# KeyBoardPower.net
KiCad netlist of a schematic drawn in Altium Designer
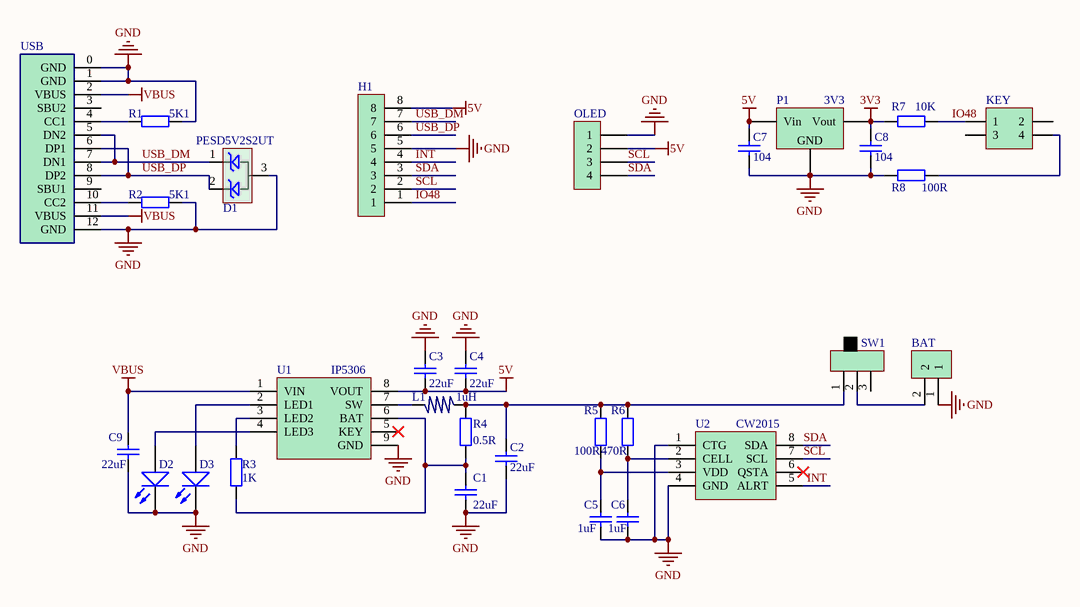
[diagram p0: KeyBoardPower.SchDoc]

(export (version "E")
  (design (tool "Eeschema 10.0.6"))
  (components
    (comp (ref "BAT")
      (value "PH2.0mm")
      (footprint "PH2.0_2P_SMT_L")
      (description "PH2.0")
      (libsource (lib "MT_Connector") (part "PH2.0mm_2P_SMT_L"))
    )
    (comp (ref "C1")
      (value "22uF")
      (footprint "0805")
      (description "贴片电容 0805")
      (libsource (lib "MT_Device") (part "CAP_0805"))
    )
    (comp (ref "C2")
      (value "22uF")
      (footprint "0805")
      (description "贴片电容 0805")
      (libsource (lib "MT_Device") (part "CAP_0805"))
    )
    (comp (ref "C3")
      (value "22uF")
      (footprint "0805")
      (description "贴片电容 0805")
      (libsource (lib "MT_Device") (part "CAP_0805"))
    )
    (comp (ref "C4")
      (value "22uF")
      (footprint "0805")
      (description "贴片电容 0805")
      (libsource (lib "MT_Device") (part "CAP_0805"))
    )
    (comp (ref "C5")
      (value "1uF")
      (footprint "0603")
      (description "贴片电容 0603")
      (libsource (lib "MT_Device") (part "CAP_0603"))
    )
    (comp (ref "C6")
      (value "1uF")
      (footprint "0603")
      (description "贴片电容 0603")
      (libsource (lib "MT_Device") (part "CAP_0603"))
    )
    (comp (ref "C7")
      (value "104")
      (footprint "0603")
      (description "贴片电容 0603")
      (libsource (lib "MT_Device") (part "CAP_0603"))
    )
    (comp (ref "C8")
      (value "104")
      (footprint "0603")
      (description "贴片电容 0603")
      (libsource (lib "MT_Device") (part "CAP_0603"))
    )
    (comp (ref "C9")
      (value "22uF")
      (footprint "0805")
      (description "贴片电容 0805")
      (libsource (lib "MT_Device") (part "CAP_0805"))
    )
    (comp (ref "D1")
      (value "PESD5V2S2UT")
      (footprint "SOT23")
      (description "ESD DIODE")
      (libsource (lib "MT_Device") (part "PESD5V2S2UT"))
    )
    (comp (ref "D2")
      (value "LED")
      (footprint "LED_0603")
      (description "LED 0603")
      (libsource (lib "MT_Device") (part "LED_0603"))
    )
    (comp (ref "D3")
      (value "LED")
      (footprint "LED_0603")
      (description "LED 0603")
      (libsource (lib "MT_Device") (part "LED_0603"))
    )
    (comp (ref "H1")
      (value "SH1.25mm_8P")
      (footprint "SH1.25MM_8P")
      (description "SH")
      (libsource (lib "MT_Connector") (part "SH1.25mm_8P"))
    )
    (comp (ref "KEY")
      (value "KEY")
      (footprint "KEY_DIP_6")
      (description "直插立式按键 6mm")
      (libsource (lib "MT_Device") (part "KEY_DIP_6"))
    )
    (comp (ref "L1")
      (value "1uH")
      (footprint "L_0420")
      (description "电感 0420")
      (libsource (lib "MT_Device") (part "L_0420"))
    )
    (comp (ref "OLED")
      (value "Header_2.54_4P")
      (footprint "HDR1_4P")
      (description "PinHeader 2.54")
      (libsource (lib "MT_Connector") (part "Header_2.54_4P"))
    )
    (comp (ref "P1")
      (value "3V3")
      (footprint "SOT23")
      (description "线性稳压器")
      (libsource (lib "MT_Device") (part "LDO_XC6206P332MR"))
    )
    (comp (ref "R1")
      (value "5K1")
      (footprint "R_0603")
      (description "电阻 0603")
      (libsource (lib "") (part "RES_0603_1"))
    )
    (comp (ref "R2")
      (value "5K1")
      (footprint "R_0603")
      (description "电阻 0603")
      (libsource (lib "") (part "RES_0603_1"))
    )
    (comp (ref "R3")
      (value "1K")
      (footprint "R_0603")
      (description "电阻 0603")
      (libsource (lib "MT_Device") (part "RES_0603"))
    )
    (comp (ref "R4")
      (value "0.5R")
      (footprint "R_0603")
      (description "电阻 0603")
      (libsource (lib "MT_Device") (part "RES_0603"))
    )
    (comp (ref "R5")
      (value "100R")
      (footprint "R_0603")
      (description "电阻 0603")
      (libsource (lib "MT_Device") (part "RES_0603"))
    )
    (comp (ref "R6")
      (value "470R")
      (footprint "R_0603")
      (description "电阻 0603")
      (libsource (lib "") (part "RES_0603_2"))
    )
    (comp (ref "R7")
      (value "10K")
      (footprint "R_0603")
      (description "电阻 0603")
      (libsource (lib "") (part "RES_0603_1"))
    )
    (comp (ref "R8")
      (value "100R")
      (footprint "R_0603")
      (description "电阻 0603")
      (libsource (lib "") (part "RES_0603_1"))
    )
    (comp (ref "SW1")
      (value "SWITCH")
      (footprint "SWITCH_SS12D10")
      (description "直插3A滑动开关")
      (libsource (lib "MT_Device") (part "SWITCH_SS12D10"))
    )
    (comp (ref "U1")
      (value "IP5306")
      (footprint "eSOP8")
      (description "电池充电")
      (libsource (lib "MT_Chip") (part "IP5306"))
    )
    (comp (ref "U2")
      (value "CW2015")
      (footprint "CW2015_TDFN")
      (description "锂电池电量计")
      (libsource (lib "MT_Chip") (part "CW2015_TDFN"))
    )
    (comp (ref "USB")
      (value "USB_C")
      (footprint "USB_C_16P_SMT")
      (description "全贴片USB C母座")
      (libsource (lib "MT_Device") (part "USB_C_16P_SMT"))
    )
  )
  (nets
    (net (code "1") (name "/INT") (class "Default")
      (node (ref "H1") (pin "4") (pinfunction "4_4") (pintype "passive"))
      (node (ref "U2") (pin "5") (pinfunction "ALRT_5") (pintype "passive"))
    )
    (net (code "2") (name "/IO48") (class "Default")
      (node (ref "H1") (pin "1") (pinfunction "1_1") (pintype "passive"))
      (node (ref "KEY") (pin "1") (pinfunction "1_1") (pintype "passive"))
      (node (ref "R7") (pin "2") (pinfunction "2_2") (pintype "passive"))
    )
    (net (code "3") (name "/SCL") (class "Default")
      (node (ref "H1") (pin "2") (pinfunction "2_2") (pintype "passive"))
      (node (ref "OLED") (pin "3") (pinfunction "3_3") (pintype "passive"))
      (node (ref "U2") (pin "7") (pinfunction "SCL_7") (pintype "passive"))
    )
    (net (code "4") (name "/SDA") (class "Default")
      (node (ref "H1") (pin "3") (pinfunction "3_3") (pintype "passive"))
      (node (ref "OLED") (pin "4") (pinfunction "4_4") (pintype "passive"))
      (node (ref "U2") (pin "8") (pinfunction "SDA_8") (pintype "passive"))
    )
    (net (code "5") (name "/USB_DM") (class "Default")
      (node (ref "D1") (pin "1") (pinfunction "1_1") (pintype "passive"))
      (node (ref "H1") (pin "7") (pinfunction "7_7") (pintype "passive"))
      (node (ref "USB") (pin "5") (pinfunction "DN2_5") (pintype "passive"))
      (node (ref "USB") (pin "7") (pinfunction "DN1_7") (pintype "passive"))
    )
    (net (code "6") (name "/USB_DP") (class "Default")
      (node (ref "D1") (pin "2") (pinfunction "2_2") (pintype "passive"))
      (node (ref "H1") (pin "6") (pinfunction "6_6") (pintype "passive"))
      (node (ref "USB") (pin "6") (pinfunction "DP1_6") (pintype "passive"))
      (node (ref "USB") (pin "8") (pinfunction "DP2_8") (pintype "passive"))
    )
    (net (code "7") (name "3V3") (class "Default")
      (node (ref "C8") (pin "2") (pinfunction "2_2") (pintype "passive"))
      (node (ref "P1") (pin "2") (pinfunction "Vout_2") (pintype "passive"))
      (node (ref "R7") (pin "1") (pinfunction "1_1") (pintype "passive"))
    )
    (net (code "8") (name "5V") (class "Default")
      (node (ref "C3") (pin "1") (pinfunction "1_1") (pintype "passive"))
      (node (ref "C4") (pin "1") (pinfunction "1_1") (pintype "passive"))
      (node (ref "C7") (pin "2") (pinfunction "2_2") (pintype "passive"))
      (node (ref "H1") (pin "8") (pinfunction "8_8") (pintype "passive"))
      (node (ref "OLED") (pin "2") (pinfunction "2_2") (pintype "passive"))
      (node (ref "P1") (pin "3") (pinfunction "Vin_3") (pintype "passive"))
      (node (ref "U1") (pin "8") (pinfunction "VOUT_8") (pintype "passive"))
    )
    (net (code "9") (name "GND") (class "Default")
      (node (ref "BAT") (pin "1") (pinfunction "1_1") (pintype "passive"))
      (node (ref "C1") (pin "1") (pinfunction "1_1") (pintype "passive"))
      (node (ref "C2") (pin "1") (pinfunction "1_1") (pintype "passive"))
      (node (ref "C3") (pin "2") (pinfunction "2_2") (pintype "passive"))
      (node (ref "C4") (pin "2") (pinfunction "2_2") (pintype "passive"))
      (node (ref "C5") (pin "1") (pinfunction "1_1") (pintype "passive"))
      (node (ref "C6") (pin "1") (pinfunction "1_1") (pintype "passive"))
      (node (ref "C7") (pin "1") (pinfunction "1_1") (pintype "passive"))
      (node (ref "C8") (pin "1") (pinfunction "1_1") (pintype "passive"))
      (node (ref "C9") (pin "1") (pinfunction "1_1") (pintype "passive"))
      (node (ref "D1") (pin "3") (pinfunction "3_3") (pintype "passive"))
      (node (ref "D2") (pin "K") (pinfunction "K_K") (pintype "passive"))
      (node (ref "D3") (pin "K") (pinfunction "K_K") (pintype "passive"))
      (node (ref "H1") (pin "5") (pinfunction "5_5") (pintype "passive"))
      (node (ref "OLED") (pin "1") (pinfunction "1_1") (pintype "passive"))
      (node (ref "P1") (pin "1") (pinfunction "GND_1") (pintype "passive"))
      (node (ref "R1") (pin "2") (pinfunction "2_2") (pintype "passive"))
      (node (ref "R2") (pin "2") (pinfunction "2_2") (pintype "passive"))
      (node (ref "R8") (pin "1") (pinfunction "1_1") (pintype "passive"))
      (node (ref "U1") (pin "9") (pinfunction "GND_9") (pintype "passive"))
      (node (ref "U2") (pin "1") (pinfunction "CTG_1") (pintype "passive"))
      (node (ref "U2") (pin "4") (pinfunction "GND_4") (pintype "passive"))
      (node (ref "USB") (pin "0") (pinfunction "GND_0") (pintype "passive"))
      (node (ref "USB") (pin "1") (pinfunction "GND_1") (pintype "passive"))
      (node (ref "USB") (pin "12") (pinfunction "GND_12") (pintype "passive"))
    )
    (net (code "10") (name "Net-(BAT-Pad2)") (class "Default")
      (node (ref "BAT") (pin "2") (pinfunction "2_2") (pintype "passive"))
      (node (ref "SW1") (pin "2") (pinfunction "2_2") (pintype "passive"))
    )
    (net (code "11") (name "Net-(C2-Pad2)") (class "Default")
      (node (ref "C2") (pin "2") (pinfunction "2_2") (pintype "passive"))
      (node (ref "L1") (pin "1") (pintype "passive"))
      (node (ref "R4") (pin "2") (pinfunction "2_2") (pintype "passive"))
      (node (ref "R5") (pin "2") (pinfunction "2_2") (pintype "passive"))
      (node (ref "R6") (pin "1") (pinfunction "1_1") (pintype "passive"))
      (node (ref "SW1") (pin "1") (pinfunction "1_1") (pintype "passive"))
    )
    (net (code "12") (name "Net-(KEY-Pad4)") (class "Default")
      (node (ref "KEY") (pin "4") (pinfunction "4_4") (pintype "passive"))
      (node (ref "R8") (pin "2") (pinfunction "2_2") (pintype "passive"))
    )
    (net (code "13") (name "Net-(U1-BAT)") (class "Default")
      (node (ref "C1") (pin "2") (pinfunction "2_2") (pintype "passive"))
      (node (ref "R3") (pin "1") (pinfunction "1_1") (pintype "passive"))
      (node (ref "R4") (pin "1") (pinfunction "1_1") (pintype "passive"))
      (node (ref "U1") (pin "6") (pinfunction "BAT_6") (pintype "passive"))
    )
    (net (code "14") (name "Net-(U1-LED1)") (class "Default")
      (node (ref "D3") (pin "A") (pinfunction "A_A") (pintype "passive"))
      (node (ref "U1") (pin "2") (pinfunction "LED1_2") (pintype "passive"))
    )
    (net (code "15") (name "Net-(U1-LED2)") (class "Default")
      (node (ref "R3") (pin "2") (pinfunction "2_2") (pintype "passive"))
      (node (ref "U1") (pin "3") (pinfunction "LED2_3") (pintype "passive"))
    )
    (net (code "16") (name "Net-(U1-LED3)") (class "Default")
      (node (ref "D2") (pin "A") (pinfunction "A_A") (pintype "passive"))
      (node (ref "U1") (pin "4") (pinfunction "LED3_4") (pintype "passive"))
    )
    (net (code "17") (name "Net-(U1-SW)") (class "Default")
      (node (ref "L1") (pin "2") (pintype "passive"))
      (node (ref "U1") (pin "7") (pinfunction "SW_7") (pintype "passive"))
    )
    (net (code "18") (name "Net-(U2-CELL)") (class "Default")
      (node (ref "C6") (pin "2") (pinfunction "2_2") (pintype "passive"))
      (node (ref "R6") (pin "2") (pinfunction "2_2") (pintype "passive"))
      (node (ref "U2") (pin "2") (pinfunction "CELL_2") (pintype "passive"))
    )
    (net (code "19") (name "Net-(U2-VDD)") (class "Default")
      (node (ref "C5") (pin "2") (pinfunction "2_2") (pintype "passive"))
      (node (ref "R5") (pin "1") (pinfunction "1_1") (pintype "passive"))
      (node (ref "U2") (pin "3") (pinfunction "VDD_3") (pintype "passive"))
    )
    (net (code "20") (name "Net-(USB-CC1)") (class "Default")
      (node (ref "R1") (pin "1") (pinfunction "1_1") (pintype "passive"))
      (node (ref "USB") (pin "4") (pinfunction "CC1_4") (pintype "passive"))
    )
    (net (code "21") (name "Net-(USB-CC2)") (class "Default")
      (node (ref "R2") (pin "1") (pinfunction "1_1") (pintype "passive"))
      (node (ref "USB") (pin "10") (pinfunction "CC2_10") (pintype "passive"))
    )
    (net (code "22") (name "VBUS") (class "Default")
      (node (ref "C9") (pin "2") (pinfunction "2_2") (pintype "passive"))
      (node (ref "U1") (pin "1") (pinfunction "VIN_1") (pintype "passive"))
      (node (ref "USB") (pin "11") (pinfunction "VBUS_11") (pintype "passive"))
      (node (ref "USB") (pin "2") (pinfunction "VBUS_2") (pintype "passive"))
    )
    (net (code "23") (name "unconnected-(KEY-Pad2)") (class "Default")
      (node (ref "KEY") (pin "2") (pinfunction "2_2") (pintype "passive"))
    )
    (net (code "24") (name "unconnected-(KEY-Pad3)") (class "Default")
      (node (ref "KEY") (pin "3") (pinfunction "3_3") (pintype "passive"))
    )
    (net (code "25") (name "unconnected-(SW1-Pad3)") (class "Default")
      (node (ref "SW1") (pin "3") (pinfunction "3_3") (pintype "passive"))
    )
    (net (code "26") (name "unconnected-(U1-KEY-Pad5)") (class "Default")
      (node (ref "U1") (pin "5") (pinfunction "KEY_5") (pintype "passive+no_connect"))
    )
    (net (code "27") (name "unconnected-(U2-QSTA-Pad6)") (class "Default")
      (node (ref "U2") (pin "6") (pinfunction "QSTA_6") (pintype "passive+no_connect"))
    )
    (net (code "28") (name "unconnected-(USB-SBU1-Pad9)") (class "Default")
      (node (ref "USB") (pin "9") (pinfunction "SBU1_9") (pintype "passive"))
    )
    (net (code "29") (name "unconnected-(USB-SBU2-Pad3)") (class "Default")
      (node (ref "USB") (pin "3") (pinfunction "SBU2_3") (pintype "passive"))
    )
  )
)
